# lipo-charger.net
KiCad netlist of a schematic drawn in EAGLE
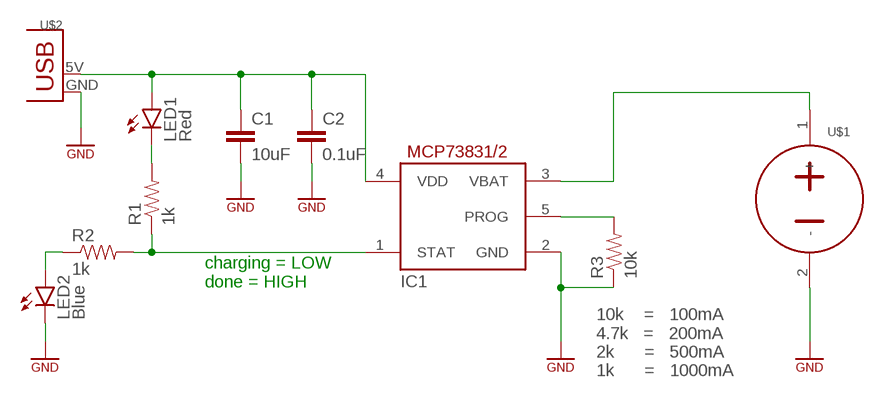
[diagram p0: schematic, sheet 1]

(export (version "E")
  (design (tool "Eeschema 10.0.6"))
  (components
    (comp (ref "C1")
      (value "10uF")
      (footprint "eagle-import:0805")
      (libsource (lib "eagle-import") (part "COMPONENT_CAP-0805"))
    )
    (comp (ref "C2")
      (value "0.1uF")
      (footprint "eagle-import:0805")
      (libsource (lib "eagle-import") (part "COMPONENT_CAP-0805"))
    )
    (comp (ref "IC1")
      (value "IC_LIPO_CHARGER")
      (footprint "eagle-import:SOT23-5")
      (libsource (lib "eagle-import") (part "IC_LIPO_CHARGER"))
    )
    (comp (ref "LED1")
      (value "Red")
      (footprint "eagle-import:CHIP-LED0805")
      (libsource (lib "eagle-import") (part "LED-0805"))
    )
    (comp (ref "LED2")
      (value "Blue")
      (footprint "eagle-import:CHIP-LED0805")
      (libsource (lib "eagle-import") (part "LED-0805"))
    )
    (comp (ref "R1")
      (value "1k")
      (footprint "eagle-import:0805")
      (libsource (lib "eagle-import") (part "COMPONENT_RESISTOR-0805"))
    )
    (comp (ref "R2")
      (value "1k")
      (footprint "eagle-import:0805")
      (libsource (lib "eagle-import") (part "COMPONENT_RESISTOR-0805"))
    )
    (comp (ref "R3")
      (value "10k")
      (footprint "eagle-import:0805")
      (libsource (lib "eagle-import") (part "COMPONENT_RESISTOR-0805"))
    )
    (comp (ref "U$1")
      (value "CONN_BATTERY-LIPO-HORIZ")
      (footprint "eagle-import:JST-PH-2-SMT-RA")
      (libsource (lib "eagle-import") (part "CONN_BATTERY-LIPO-HORIZ"))
    )
    (comp (ref "U$2")
      (value "CONN_USB_PCB_POWER")
      (footprint "eagle-import:USB-PCB-POWER")
      (libsource (lib "eagle-import") (part "CONN_USB_PCB_POWER"))
    )
  )
  (nets
    (net (code "1") (name "Net-(IC1-PROG)") (class "Default")
      (node (ref "IC1") (pin "5") (pinfunction "PROG_5") (pintype "input"))
      (node (ref "R3") (pin "2") (pinfunction "2_2") (pintype "passive"))
    )
    (net (code "2") (name "Net-(IC1-STAT)") (class "Default")
      (node (ref "IC1") (pin "1") (pinfunction "STAT_1") (pintype "output"))
      (node (ref "R1") (pin "1") (pinfunction "1_1") (pintype "passive"))
      (node (ref "R2") (pin "2") (pinfunction "2_2") (pintype "passive"))
    )
    (net (code "3") (name "Net-(IC1-VBAT)") (class "Default")
      (node (ref "IC1") (pin "3") (pinfunction "VBAT_3") (pintype "bidirectional"))
      (node (ref "U$1") (pin "1") (pinfunction "+_1") (pintype "bidirectional"))
    )
    (net (code "4") (name "Net-(IC1-VDD)") (class "Default")
      (node (ref "C1") (pin "1") (pinfunction "1_1") (pintype "passive"))
      (node (ref "C2") (pin "1") (pinfunction "1_1") (pintype "passive"))
      (node (ref "IC1") (pin "4") (pinfunction "VDD_4") (pintype "power_in"))
      (node (ref "LED1") (pin "A") (pinfunction "A_A") (pintype "passive"))
      (node (ref "U$2") (pin "5V") (pinfunction "VBUS_5V") (pintype "bidirectional"))
    )
    (net (code "5") (name "Net-(LED1-PadC)") (class "Default")
      (node (ref "LED1") (pin "C") (pinfunction "C_C") (pintype "passive"))
      (node (ref "R1") (pin "2") (pinfunction "2_2") (pintype "passive"))
    )
    (net (code "6") (name "Net-(LED2-PadA)") (class "Default")
      (node (ref "LED2") (pin "A") (pinfunction "A_A") (pintype "passive"))
      (node (ref "R2") (pin "1") (pinfunction "1_1") (pintype "passive"))
    )
    (net (code "7") (name "SYMBOL_GND") (class "Default")
      (node (ref "C1") (pin "2") (pinfunction "2_2") (pintype "passive"))
      (node (ref "C2") (pin "2") (pinfunction "2_2") (pintype "passive"))
      (node (ref "IC1") (pin "2") (pinfunction "GND_2") (pintype "power_in"))
      (node (ref "LED2") (pin "C") (pinfunction "C_C") (pintype "passive"))
      (node (ref "R3") (pin "1") (pinfunction "1_1") (pintype "passive"))
      (node (ref "U$1") (pin "2") (pinfunction "-_2") (pintype "bidirectional"))
      (node (ref "U$2") (pin "GND") (pinfunction "GND_GND") (pintype "bidirectional"))
    )
  )
)
